# audio.net
KiCad netlist of a schematic drawn in Altium Designer
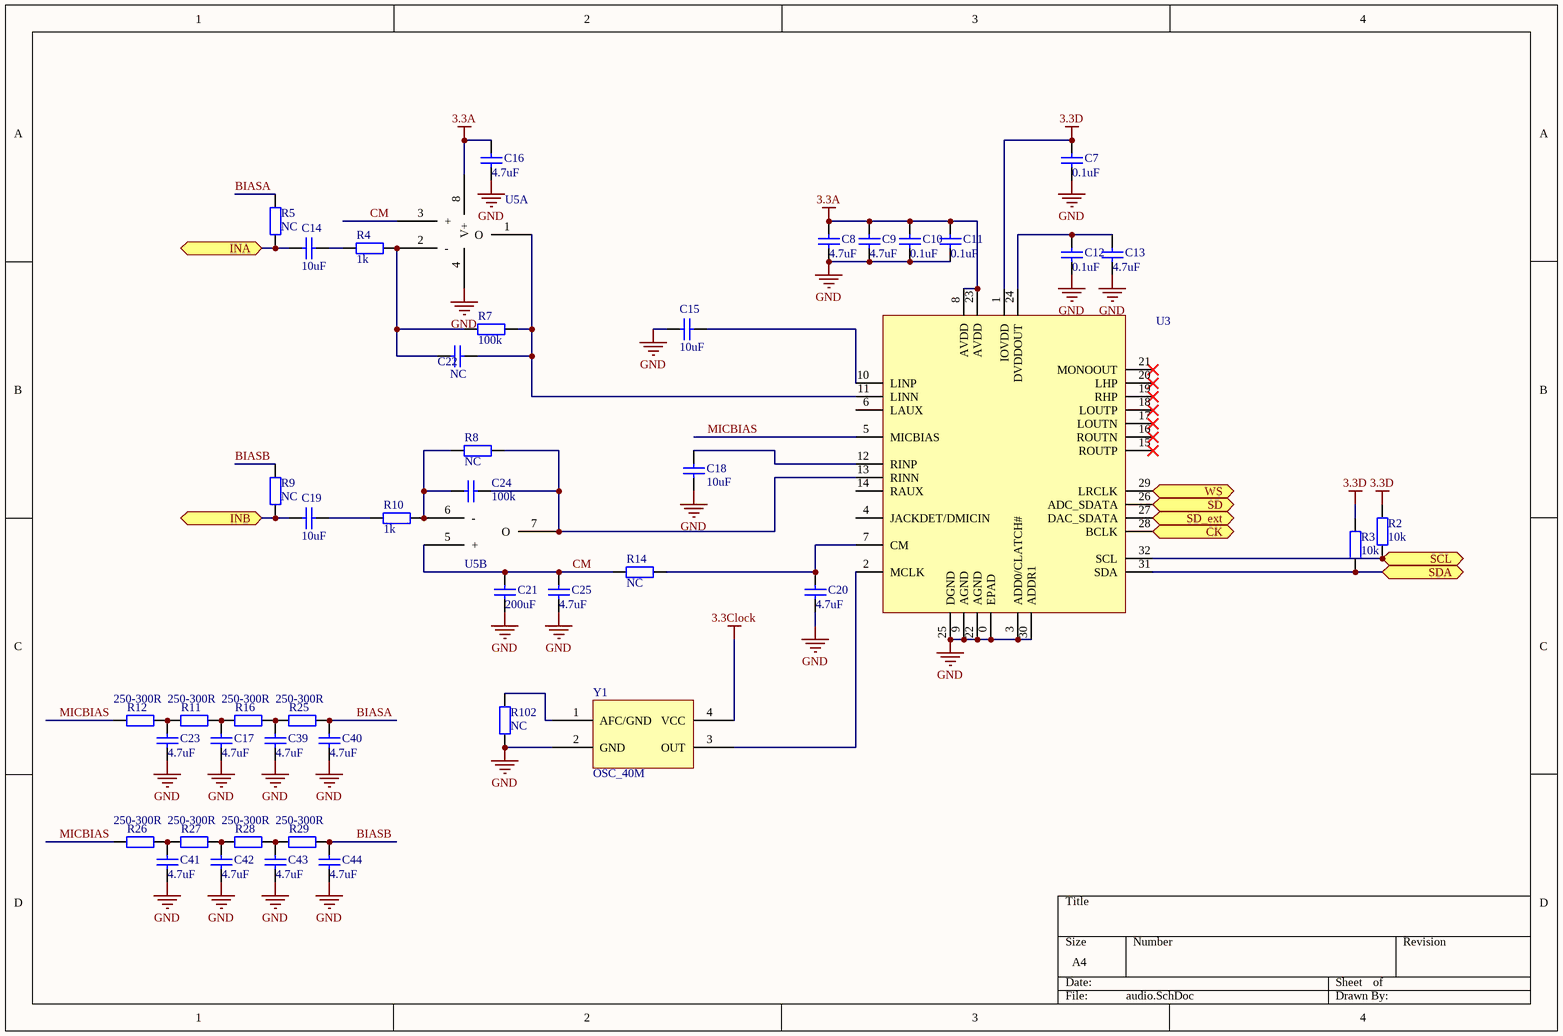
[diagram p0: audio.SchDoc]

(export (version "E")
  (design (tool "Eeschema 10.0.6"))
  (components
    (comp (ref "C7")
      (value "0.1uF")
      (footprint "0402")
      (description "Capacitor")
      (fields (field (name "PUBLISHER") "Altium Limited"))
      (libsource (lib "RTC6705") (part "Cap"))
    )
    (comp (ref "C8")
      (value "4.7uF")
      (footprint "0805")
      (description "Capacitor")
      (fields (field (name "PUBLISHER") "Altium Limited"))
      (libsource (lib "RTC6705") (part "Cap"))
    )
    (comp (ref "C9")
      (value "4.7uF")
      (footprint "0805")
      (description "Capacitor")
      (fields (field (name "PUBLISHER") "Altium Limited"))
      (libsource (lib "RTC6705") (part "Cap"))
    )
    (comp (ref "C10")
      (value "0.1uF")
      (footprint "0402")
      (description "Capacitor")
      (fields (field (name "PUBLISHER") "Altium Limited"))
      (libsource (lib "RTC6705") (part "Cap"))
    )
    (comp (ref "C11")
      (value "0.1uF")
      (footprint "0402")
      (description "Capacitor")
      (fields (field (name "PUBLISHER") "Altium Limited"))
      (libsource (lib "RTC6705") (part "Cap"))
    )
    (comp (ref "C12")
      (value "0.1uF")
      (footprint "0402")
      (description "Capacitor")
      (fields (field (name "PUBLISHER") "Altium Limited"))
      (libsource (lib "RTC6705") (part "Cap"))
    )
    (comp (ref "C13")
      (value "4.7uF")
      (footprint "0805")
      (description "Capacitor")
      (fields (field (name "PUBLISHER") "Altium Limited"))
      (libsource (lib "RTC6705") (part "Cap"))
    )
    (comp (ref "C14")
      (value "10uF")
      (footprint "CL21-5mm-1F")
      (description "Capacitor")
      (fields (field (name "PUBLISHER") "Altium Limited"))
      (libsource (lib "RTC6705") (part "Cap"))
    )
    (comp (ref "C15")
      (value "10uF")
      (footprint "0805")
      (description "Capacitor")
      (fields (field (name "PUBLISHER") "Altium Limited"))
      (libsource (lib "RTC6705") (part "Cap"))
    )
    (comp (ref "C16")
      (value "4.7uF")
      (footprint "0805")
      (description "Capacitor")
      (fields (field (name "PUBLISHER") "Altium Limited"))
      (libsource (lib "RTC6705") (part "Cap"))
    )
    (comp (ref "C17")
      (value "4.7uF")
      (footprint "0805")
      (description "Capacitor")
      (fields (field (name "PUBLISHER") "Altium Limited"))
      (libsource (lib "RTC6705") (part "Cap"))
    )
    (comp (ref "C18")
      (value "10uF")
      (footprint "0805")
      (description "Capacitor")
      (fields (field (name "PUBLISHER") "Altium Limited"))
      (libsource (lib "RTC6705") (part "Cap"))
    )
    (comp (ref "C19")
      (value "10uF")
      (footprint "CL21-5mm-1F")
      (description "Capacitor")
      (fields (field (name "PUBLISHER") "Altium Limited"))
      (libsource (lib "RTC6705") (part "Cap"))
    )
    (comp (ref "C20")
      (value "4.7uF")
      (footprint "0805")
      (description "Capacitor")
      (fields (field (name "PUBLISHER") "Altium Limited"))
      (libsource (lib "RTC6705") (part "Cap"))
    )
    (comp (ref "C21")
      (value "200uF")
      (footprint "1210")
      (description "Capacitor")
      (fields (field (name "PUBLISHER") "Altium Limited"))
      (libsource (lib "RTC6705") (part "Cap"))
    )
    (comp (ref "C22")
      (value "NC")
      (footprint "0402")
      (description "Capacitor")
      (fields (field (name "PUBLISHER") "Altium Limited"))
      (libsource (lib "RTC6705") (part "Cap"))
    )
    (comp (ref "C23")
      (value "4.7uF")
      (footprint "0805")
      (description "Capacitor")
      (fields (field (name "PUBLISHER") "Altium Limited"))
      (libsource (lib "RTC6705") (part "Cap"))
    )
    (comp (ref "C24")
      (value "100k")
      (footprint "0402")
      (description "Capacitor")
      (fields (field (name "PUBLISHER") "Altium Limited"))
      (libsource (lib "RTC6705") (part "Cap"))
    )
    (comp (ref "C25")
      (value "4.7uF")
      (footprint "0805")
      (description "Capacitor")
      (fields (field (name "PUBLISHER") "Altium Limited"))
      (libsource (lib "RTC6705") (part "Cap"))
    )
    (comp (ref "C39")
      (value "4.7uF")
      (footprint "0805")
      (description "Capacitor")
      (fields (field (name "PUBLISHER") "Altium Limited"))
      (libsource (lib "RTC6705") (part "Cap"))
    )
    (comp (ref "C40")
      (value "4.7uF")
      (footprint "0805")
      (description "Capacitor")
      (fields (field (name "PUBLISHER") "Altium Limited"))
      (libsource (lib "RTC6705") (part "Cap"))
    )
    (comp (ref "C41")
      (value "4.7uF")
      (footprint "0805")
      (description "Capacitor")
      (fields (field (name "PUBLISHER") "Altium Limited"))
      (libsource (lib "RTC6705") (part "Cap"))
    )
    (comp (ref "C42")
      (value "4.7uF")
      (footprint "0805")
      (description "Capacitor")
      (fields (field (name "PUBLISHER") "Altium Limited"))
      (libsource (lib "RTC6705") (part "Cap"))
    )
    (comp (ref "C43")
      (value "4.7uF")
      (footprint "0805")
      (description "Capacitor")
      (fields (field (name "PUBLISHER") "Altium Limited"))
      (libsource (lib "RTC6705") (part "Cap"))
    )
    (comp (ref "C44")
      (value "4.7uF")
      (footprint "0805")
      (description "Capacitor")
      (fields (field (name "PUBLISHER") "Altium Limited"))
      (libsource (lib "RTC6705") (part "Cap"))
    )
    (comp (ref "R2")
      (value "10k")
      (footprint "0402")
      (description "Resistor")
      (fields (field (name "Comment") "Res2") (field (name "PUBLISHER") "Altium Limited"))
      (libsource (lib "RTC6705") (part "Res2"))
    )
    (comp (ref "R3")
      (value "10k")
      (footprint "0402")
      (description "Resistor")
      (fields (field (name "Comment") "Res2") (field (name "PUBLISHER") "Altium Limited"))
      (libsource (lib "RTC6705") (part "Res2"))
    )
    (comp (ref "R4")
      (value "1k")
      (footprint "0402")
      (description "Resistor")
      (fields (field (name "PUBLISHER") "Altium Limited"))
      (libsource (lib "") (part "Res2_2"))
    )
    (comp (ref "R5")
      (value "NC")
      (footprint "0402")
      (description "Resistor")
      (fields (field (name "PUBLISHER") "Altium Limited"))
      (libsource (lib "") (part "Res2_3"))
    )
    (comp (ref "R7")
      (value "100k")
      (footprint "0402")
      (description "Resistor")
      (fields (field (name "PUBLISHER") "Altium Limited"))
      (libsource (lib "") (part "Res2_2"))
    )
    (comp (ref "R8")
      (value "NC")
      (footprint "0402")
      (description "Resistor")
      (fields (field (name "PUBLISHER") "Altium Limited"))
      (libsource (lib "") (part "Res2_2"))
    )
    (comp (ref "R9")
      (value "NC")
      (footprint "0402")
      (description "Resistor")
      (fields (field (name "PUBLISHER") "Altium Limited"))
      (libsource (lib "") (part "Res2_3"))
    )
    (comp (ref "R10")
      (value "1k")
      (footprint "0402")
      (description "Resistor")
      (fields (field (name "PUBLISHER") "Altium Limited"))
      (libsource (lib "") (part "Res2_2"))
    )
    (comp (ref "R11")
      (value "250-300R")
      (footprint "0402")
      (description "Resistor")
      (fields (field (name "PUBLISHER") "Altium Limited"))
      (libsource (lib "") (part "Res2_1"))
    )
    (comp (ref "R12")
      (value "250-300R")
      (footprint "0402")
      (description "Resistor")
      (fields (field (name "PUBLISHER") "Altium Limited"))
      (libsource (lib "") (part "Res2_1"))
    )
    (comp (ref "R14")
      (value "NC")
      (footprint "0402")
      (description "Resistor")
      (fields (field (name "PUBLISHER") "Altium Limited"))
      (libsource (lib "") (part "Res2_1"))
    )
    (comp (ref "R16")
      (value "250-300R")
      (footprint "0402")
      (description "Resistor")
      (fields (field (name "PUBLISHER") "Altium Limited"))
      (libsource (lib "") (part "Res2_1"))
    )
    (comp (ref "R25")
      (value "250-300R")
      (footprint "0402")
      (description "Resistor")
      (fields (field (name "PUBLISHER") "Altium Limited"))
      (libsource (lib "") (part "Res2_1"))
    )
    (comp (ref "R26")
      (value "250-300R")
      (footprint "0402")
      (description "Resistor")
      (fields (field (name "PUBLISHER") "Altium Limited"))
      (libsource (lib "") (part "Res2_1"))
    )
    (comp (ref "R27")
      (value "250-300R")
      (footprint "0402")
      (description "Resistor")
      (fields (field (name "PUBLISHER") "Altium Limited"))
      (libsource (lib "") (part "Res2_1"))
    )
    (comp (ref "R28")
      (value "250-300R")
      (footprint "0402")
      (description "Resistor")
      (fields (field (name "PUBLISHER") "Altium Limited"))
      (libsource (lib "") (part "Res2_1"))
    )
    (comp (ref "R29")
      (value "250-300R")
      (footprint "0402")
      (description "Resistor")
      (fields (field (name "PUBLISHER") "Altium Limited"))
      (libsource (lib "") (part "Res2_1"))
    )
    (comp (ref "R102")
      (value "NC")
      (footprint "0402")
      (description "Resistor")
      (fields (field (name "PUBLISHER") "Altium Limited"))
      (libsource (lib "Miscellaneous Devices") (part "Res2"))
    )
    (comp (ref "U3") (value "ADAU1761") (footprint "ADAU1761") (libsource (lib "ADAU1761") (part "ADAU1761")))
    (comp (ref "U5") (value "OP-2") (footprint "SO8") (libsource (lib "ADAU1761") (part "OP-2")))
    (comp (ref "Y1") (value "OSC_40M") (footprint "TXC_7Q") (libsource (lib "F4SDR") (part "OSC_40M")))
  )
  (nets
    (net (code "1") (name "/BIASA") (class "Default")
      (node (ref "C40") (pin "2") (pinfunction "2_2") (pintype "passive"))
      (node (ref "R25") (pin "1") (pinfunction "1_1") (pintype "passive"))
      (node (ref "R5") (pin "2") (pinfunction "2_2") (pintype "passive"))
    )
    (net (code "2") (name "/BIASB") (class "Default")
      (node (ref "C44") (pin "2") (pinfunction "2_2") (pintype "passive"))
      (node (ref "R29") (pin "1") (pinfunction "1_1") (pintype "passive"))
      (node (ref "R9") (pin "2") (pinfunction "2_2") (pintype "passive"))
    )
    (net (code "3") (name "/CK") (class "Default")
      (node (ref "U3") (pin "28") (pinfunction "BCLK_28") (pintype "passive"))
    )
    (net (code "4") (name "/CM") (class "Default")
      (node (ref "C21") (pin "2") (pinfunction "2_2") (pintype "passive"))
      (node (ref "C25") (pin "2") (pinfunction "2_2") (pintype "passive"))
      (node (ref "R14") (pin "2") (pinfunction "2_2") (pintype "passive"))
      (node (ref "U5") (pin "3") (pinfunction "+_3") (pintype "passive"))
      (node (ref "U5") (pin "5") (pinfunction "+_5") (pintype "passive"))
    )
    (net (code "5") (name "/INA") (class "Default")
      (node (ref "C14") (pin "2") (pinfunction "2_2") (pintype "passive"))
      (node (ref "R5") (pin "1") (pinfunction "1_1") (pintype "passive"))
    )
    (net (code "6") (name "/INB") (class "Default")
      (node (ref "C19") (pin "2") (pinfunction "2_2") (pintype "passive"))
      (node (ref "R9") (pin "1") (pinfunction "1_1") (pintype "passive"))
    )
    (net (code "7") (name "/MICBIAS") (class "Default")
      (node (ref "R12") (pin "2") (pinfunction "2_2") (pintype "passive"))
      (node (ref "R26") (pin "2") (pinfunction "2_2") (pintype "passive"))
      (node (ref "U3") (pin "5") (pinfunction "MICBIAS_5") (pintype "passive"))
    )
    (net (code "8") (name "/SCL") (class "Default")
      (node (ref "R2") (pin "1") (pinfunction "1_1") (pintype "passive"))
      (node (ref "U3") (pin "32") (pinfunction "SCL_32") (pintype "passive"))
    )
    (net (code "9") (name "/SD") (class "Default")
      (node (ref "U3") (pin "26") (pinfunction "ADC_SDATA_26") (pintype "passive"))
    )
    (net (code "10") (name "/SDA") (class "Default")
      (node (ref "R3") (pin "1") (pinfunction "1_1") (pintype "passive"))
      (node (ref "U3") (pin "31") (pinfunction "SDA_31") (pintype "passive"))
    )
    (net (code "11") (name "/SD_ext") (class "Default")
      (node (ref "U3") (pin "27") (pinfunction "DAC_SDATA_27") (pintype "passive"))
    )
    (net (code "12") (name "/WS") (class "Default")
      (node (ref "U3") (pin "29") (pinfunction "LRCLK_29") (pintype "passive"))
    )
    (net (code "13") (name "3.3A") (class "Default")
      (node (ref "C10") (pin "2") (pinfunction "2_2") (pintype "passive"))
      (node (ref "C11") (pin "2") (pinfunction "2_2") (pintype "passive"))
      (node (ref "C16") (pin "2") (pinfunction "2_2") (pintype "passive"))
      (node (ref "C8") (pin "2") (pinfunction "2_2") (pintype "passive"))
      (node (ref "C9") (pin "2") (pinfunction "2_2") (pintype "passive"))
      (node (ref "U3") (pin "23") (pinfunction "AVDD_23") (pintype "passive"))
      (node (ref "U3") (pin "8") (pinfunction "AVDD_8") (pintype "passive"))
      (node (ref "U5") (pin "8") (pinfunction "V+_8") (pintype "passive"))
    )
    (net (code "14") (name "3.3Clock") (class "Default")
      (node (ref "Y1") (pin "4") (pinfunction "VCC_4") (pintype "passive"))
    )
    (net (code "15") (name "3.3D") (class "Default")
      (node (ref "C7") (pin "2") (pinfunction "2_2") (pintype "passive"))
      (node (ref "R2") (pin "2") (pinfunction "2_2") (pintype "passive"))
      (node (ref "R3") (pin "2") (pinfunction "2_2") (pintype "passive"))
      (node (ref "U3") (pin "1") (pinfunction "IOVDD_1") (pintype "passive"))
    )
    (net (code "16") (name "GND") (class "Default")
      (node (ref "C10") (pin "1") (pinfunction "1_1") (pintype "passive"))
      (node (ref "C11") (pin "1") (pinfunction "1_1") (pintype "passive"))
      (node (ref "C12") (pin "1") (pinfunction "1_1") (pintype "passive"))
      (node (ref "C13") (pin "1") (pinfunction "1_1") (pintype "passive"))
      (node (ref "C15") (pin "2") (pinfunction "2_2") (pintype "passive"))
      (node (ref "C16") (pin "1") (pinfunction "1_1") (pintype "passive"))
      (node (ref "C17") (pin "1") (pinfunction "1_1") (pintype "passive"))
      (node (ref "C18") (pin "1") (pinfunction "1_1") (pintype "passive"))
      (node (ref "C20") (pin "1") (pinfunction "1_1") (pintype "passive"))
      (node (ref "C21") (pin "1") (pinfunction "1_1") (pintype "passive"))
      (node (ref "C23") (pin "1") (pinfunction "1_1") (pintype "passive"))
      (node (ref "C25") (pin "1") (pinfunction "1_1") (pintype "passive"))
      (node (ref "C39") (pin "1") (pinfunction "1_1") (pintype "passive"))
      (node (ref "C40") (pin "1") (pinfunction "1_1") (pintype "passive"))
      (node (ref "C41") (pin "1") (pinfunction "1_1") (pintype "passive"))
      (node (ref "C42") (pin "1") (pinfunction "1_1") (pintype "passive"))
      (node (ref "C43") (pin "1") (pinfunction "1_1") (pintype "passive"))
      (node (ref "C44") (pin "1") (pinfunction "1_1") (pintype "passive"))
      (node (ref "C7") (pin "1") (pinfunction "1_1") (pintype "passive"))
      (node (ref "C8") (pin "1") (pinfunction "1_1") (pintype "passive"))
      (node (ref "C9") (pin "1") (pinfunction "1_1") (pintype "passive"))
      (node (ref "R102") (pin "2") (pinfunction "2_2") (pintype "passive"))
      (node (ref "U3") (pin "0") (pinfunction "EPAD_0") (pintype "passive"))
      (node (ref "U3") (pin "22") (pinfunction "AGND_22") (pintype "passive"))
      (node (ref "U3") (pin "25") (pinfunction "DGND_25") (pintype "passive"))
      (node (ref "U3") (pin "3") (pinfunction "ADD0/CLATCH#_3") (pintype "passive"))
      (node (ref "U3") (pin "30") (pinfunction "ADDR1_30") (pintype "passive"))
      (node (ref "U3") (pin "9") (pinfunction "AGND_9") (pintype "passive"))
      (node (ref "U5") (pin "4") (pinfunction "5_4") (pintype "passive"))
      (node (ref "Y1") (pin "2") (pinfunction "GND_2") (pintype "passive"))
    )
    (net (code "17") (name "Net-(C14-Pad1)") (class "Default")
      (node (ref "C14") (pin "1") (pinfunction "1_1") (pintype "passive"))
      (node (ref "R4") (pin "1") (pinfunction "1_1") (pintype "passive"))
    )
    (net (code "18") (name "Net-(C17-Pad2)") (class "Default")
      (node (ref "C17") (pin "2") (pinfunction "2_2") (pintype "passive"))
      (node (ref "R11") (pin "1") (pinfunction "1_1") (pintype "passive"))
      (node (ref "R16") (pin "2") (pinfunction "2_2") (pintype "passive"))
    )
    (net (code "19") (name "Net-(C19-Pad1)") (class "Default")
      (node (ref "C19") (pin "1") (pinfunction "1_1") (pintype "passive"))
      (node (ref "R10") (pin "1") (pinfunction "1_1") (pintype "passive"))
    )
    (net (code "20") (name "Net-(C23-Pad2)") (class "Default")
      (node (ref "C23") (pin "2") (pinfunction "2_2") (pintype "passive"))
      (node (ref "R11") (pin "2") (pinfunction "2_2") (pintype "passive"))
      (node (ref "R12") (pin "1") (pinfunction "1_1") (pintype "passive"))
    )
    (net (code "21") (name "Net-(C39-Pad2)") (class "Default")
      (node (ref "C39") (pin "2") (pinfunction "2_2") (pintype "passive"))
      (node (ref "R16") (pin "1") (pinfunction "1_1") (pintype "passive"))
      (node (ref "R25") (pin "2") (pinfunction "2_2") (pintype "passive"))
    )
    (net (code "22") (name "Net-(C41-Pad2)") (class "Default")
      (node (ref "C41") (pin "2") (pinfunction "2_2") (pintype "passive"))
      (node (ref "R26") (pin "1") (pinfunction "1_1") (pintype "passive"))
      (node (ref "R27") (pin "2") (pinfunction "2_2") (pintype "passive"))
    )
    (net (code "23") (name "Net-(C42-Pad2)") (class "Default")
      (node (ref "C42") (pin "2") (pinfunction "2_2") (pintype "passive"))
      (node (ref "R27") (pin "1") (pinfunction "1_1") (pintype "passive"))
      (node (ref "R28") (pin "2") (pinfunction "2_2") (pintype "passive"))
    )
    (net (code "24") (name "Net-(C43-Pad2)") (class "Default")
      (node (ref "C43") (pin "2") (pinfunction "2_2") (pintype "passive"))
      (node (ref "R28") (pin "1") (pinfunction "1_1") (pintype "passive"))
      (node (ref "R29") (pin "2") (pinfunction "2_2") (pintype "passive"))
    )
    (net (code "25") (name "Net-(U3-CM)") (class "Default")
      (node (ref "C20") (pin "2") (pinfunction "2_2") (pintype "passive"))
      (node (ref "R14") (pin "1") (pinfunction "1_1") (pintype "passive"))
      (node (ref "U3") (pin "7") (pinfunction "CM_7") (pintype "passive"))
    )
    (net (code "26") (name "Net-(U3-DVDDOUT)") (class "Default")
      (node (ref "C12") (pin "2") (pinfunction "2_2") (pintype "passive"))
      (node (ref "C13") (pin "2") (pinfunction "2_2") (pintype "passive"))
      (node (ref "U3") (pin "24") (pinfunction "DVDDOUT_24") (pintype "passive"))
    )
    (net (code "27") (name "Net-(U3-LINN)") (class "Default")
      (node (ref "C22") (pin "1") (pinfunction "1_1") (pintype "passive"))
      (node (ref "R7") (pin "2") (pinfunction "2_2") (pintype "passive"))
      (node (ref "U3") (pin "11") (pinfunction "LINN_11") (pintype "passive"))
      (node (ref "U5") (pin "1") (pinfunction "O_1") (pintype "passive"))
    )
    (net (code "28") (name "Net-(U3-LINP)") (class "Default")
      (node (ref "C15") (pin "1") (pinfunction "1_1") (pintype "passive"))
      (node (ref "U3") (pin "10") (pinfunction "LINP_10") (pintype "passive"))
    )
    (net (code "29") (name "Net-(U3-MCLK)") (class "Default")
      (node (ref "U3") (pin "2") (pinfunction "MCLK_2") (pintype "passive"))
      (node (ref "Y1") (pin "3") (pinfunction "OUT_3") (pintype "passive"))
    )
    (net (code "30") (name "Net-(U3-RINN)") (class "Default")
      (node (ref "C24") (pin "1") (pinfunction "1_1") (pintype "passive"))
      (node (ref "R8") (pin "2") (pinfunction "2_2") (pintype "passive"))
      (node (ref "U3") (pin "13") (pinfunction "RINN_13") (pintype "passive"))
      (node (ref "U5") (pin "7") (pinfunction "O_7") (pintype "passive"))
    )
    (net (code "31") (name "Net-(U3-RINP)") (class "Default")
      (node (ref "C18") (pin "2") (pinfunction "2_2") (pintype "passive"))
      (node (ref "U3") (pin "12") (pinfunction "RINP_12") (pintype "passive"))
    )
    (net (code "32") (name "Net-(U5A--)") (class "Default")
      (node (ref "C22") (pin "2") (pinfunction "2_2") (pintype "passive"))
      (node (ref "R4") (pin "2") (pinfunction "2_2") (pintype "passive"))
      (node (ref "R7") (pin "1") (pinfunction "1_1") (pintype "passive"))
      (node (ref "U5") (pin "2") (pinfunction "-_2") (pintype "passive"))
    )
    (net (code "33") (name "Net-(U5B--)") (class "Default")
      (node (ref "C24") (pin "2") (pinfunction "2_2") (pintype "passive"))
      (node (ref "R10") (pin "2") (pinfunction "2_2") (pintype "passive"))
      (node (ref "R8") (pin "1") (pinfunction "1_1") (pintype "passive"))
      (node (ref "U5") (pin "6") (pinfunction "-_6") (pintype "passive"))
    )
    (net (code "34") (name "Net-(Y1-AFC{slash}GND)") (class "Default")
      (node (ref "R102") (pin "1") (pinfunction "1_1") (pintype "passive"))
      (node (ref "Y1") (pin "1") (pinfunction "AFC/GND_1") (pintype "passive"))
    )
    (net (code "35") (name "unconnected-(U3-JACKDET{slash}DMICIN-Pad4)") (class "Default")
      (node (ref "U3") (pin "4") (pinfunction "JACKDET/DMICIN_4") (pintype "passive"))
    )
    (net (code "36") (name "unconnected-(U3-LAUX-Pad6)") (class "Default")
      (node (ref "U3") (pin "6") (pinfunction "LAUX_6") (pintype "passive"))
    )
    (net (code "37") (name "unconnected-(U3-LHP-Pad20)") (class "Default")
      (node (ref "U3") (pin "20") (pinfunction "LHP_20") (pintype "passive+no_connect"))
    )
    (net (code "38") (name "unconnected-(U3-LOUTN-Pad17)") (class "Default")
      (node (ref "U3") (pin "17") (pinfunction "LOUTN_17") (pintype "passive+no_connect"))
    )
    (net (code "39") (name "unconnected-(U3-LOUTP-Pad18)") (class "Default")
      (node (ref "U3") (pin "18") (pinfunction "LOUTP_18") (pintype "passive+no_connect"))
    )
    (net (code "40") (name "unconnected-(U3-MONOOUT-Pad21)") (class "Default")
      (node (ref "U3") (pin "21") (pinfunction "MONOOUT_21") (pintype "passive+no_connect"))
    )
    (net (code "41") (name "unconnected-(U3-RAUX-Pad14)") (class "Default")
      (node (ref "U3") (pin "14") (pinfunction "RAUX_14") (pintype "passive"))
    )
    (net (code "42") (name "unconnected-(U3-RHP-Pad19)") (class "Default")
      (node (ref "U3") (pin "19") (pinfunction "RHP_19") (pintype "passive+no_connect"))
    )
    (net (code "43") (name "unconnected-(U3-ROUTN-Pad16)") (class "Default")
      (node (ref "U3") (pin "16") (pinfunction "ROUTN_16") (pintype "passive+no_connect"))
    )
    (net (code "44") (name "unconnected-(U3-ROUTP-Pad15)") (class "Default")
      (node (ref "U3") (pin "15") (pinfunction "ROUTP_15") (pintype "passive+no_connect"))
    )
  )
)
